# hvreg_feedback_2PS_FS_F.net
KiCad netlist of a schematic drawn in EAGLE
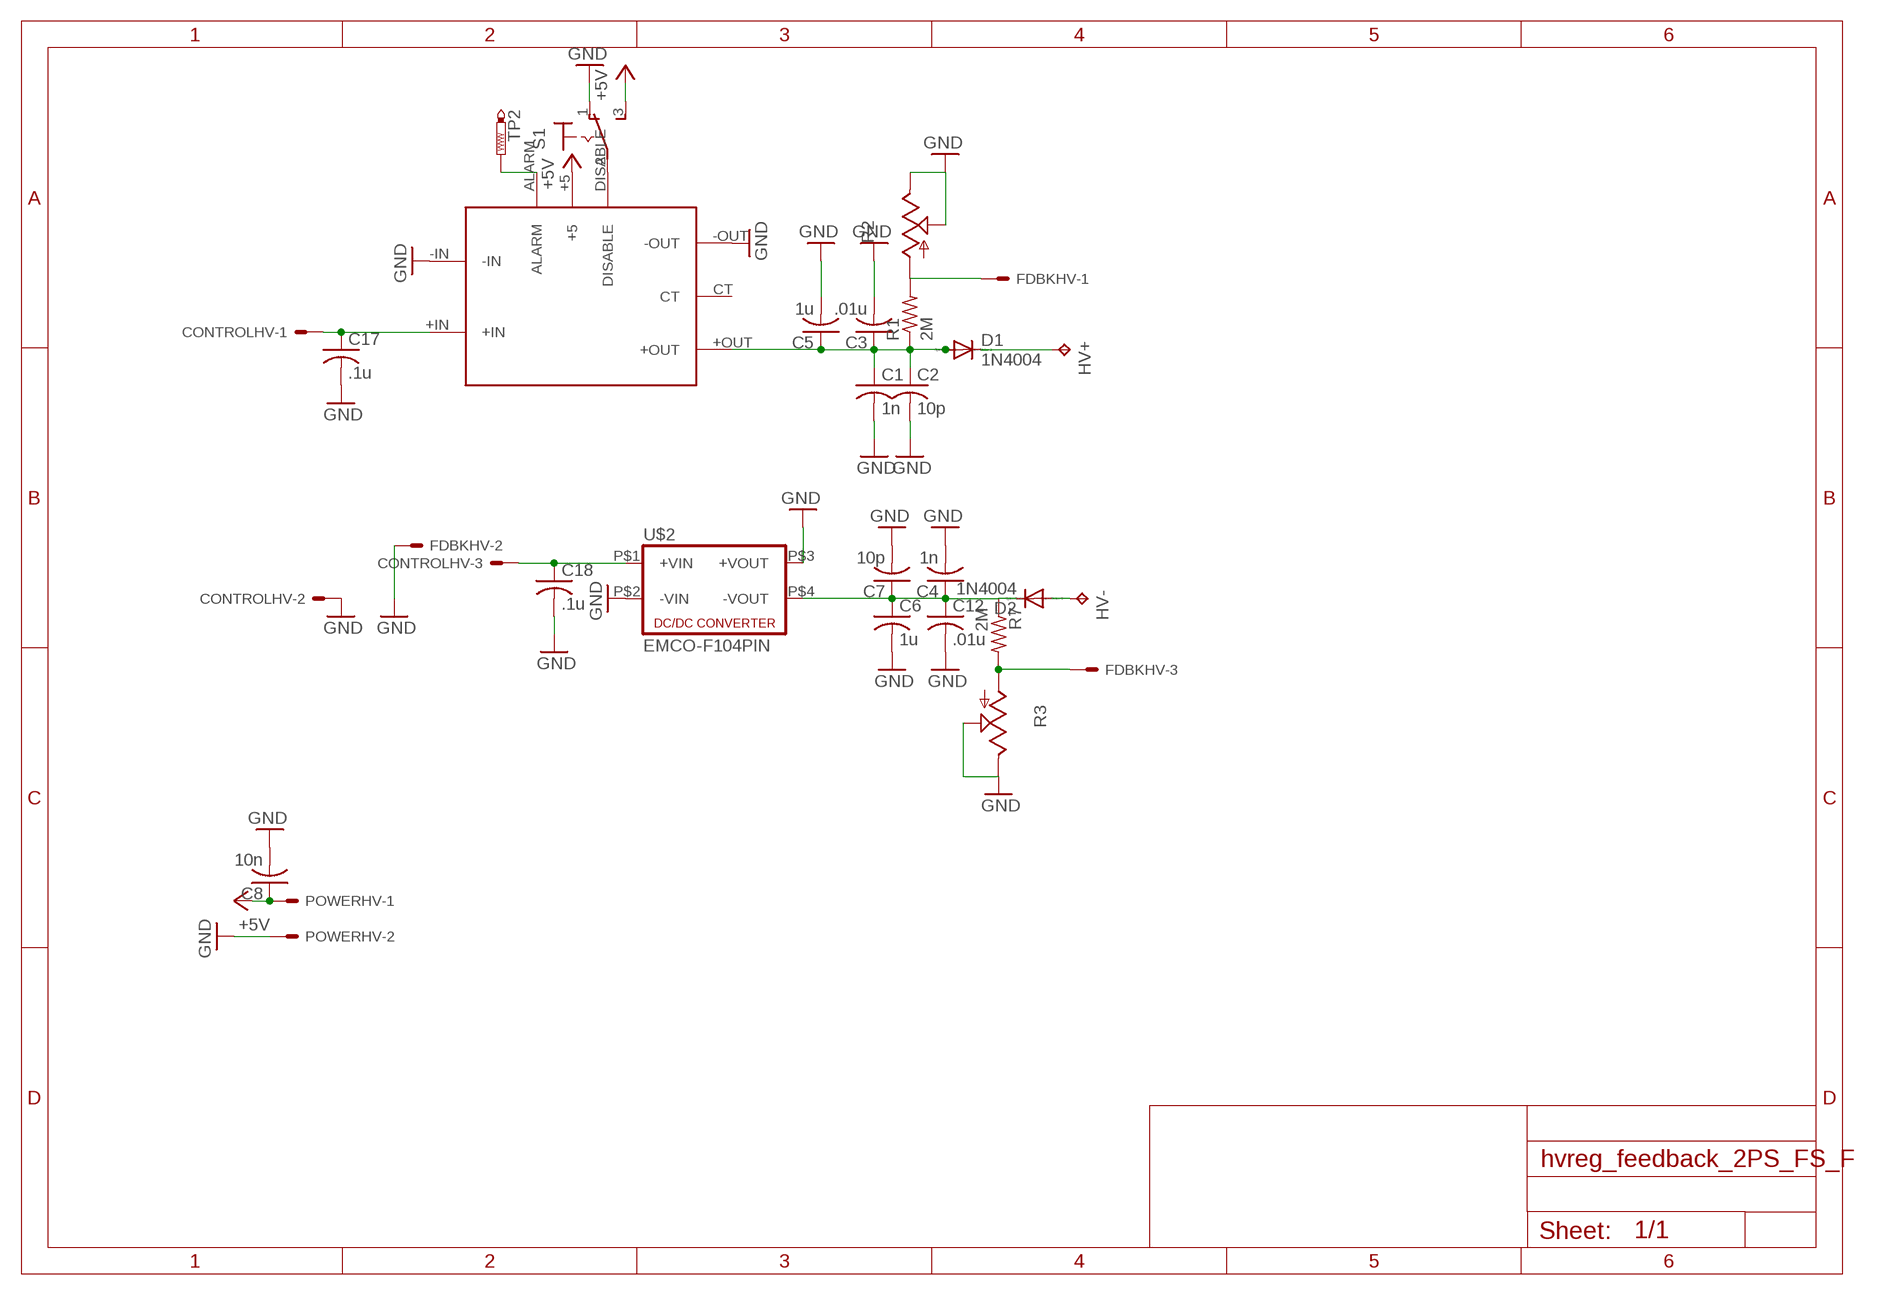
[diagram p0: schematic, sheet 1]

(export (version "E")
  (design (tool "Eeschema 10.0.6"))
  (components
    (comp (ref "C1")
      (value "1n")
      (footprint "eagle-import:C102-043X133")
      (libsource (lib "eagle-import") (part "C-US102-043X133"))
    )
    (comp (ref "C2")
      (value "10p")
      (footprint "eagle-import:C102-043X133")
      (libsource (lib "eagle-import") (part "C-US102-043X133"))
    )
    (comp (ref "C3")
      (value ".01u")
      (footprint "eagle-import:C102-043X133")
      (libsource (lib "eagle-import") (part "C-US102-043X133"))
    )
    (comp (ref "C4")
      (value "1n")
      (footprint "eagle-import:C102-043X133")
      (libsource (lib "eagle-import") (part "C-US102-043X133"))
    )
    (comp (ref "C5")
      (value "1u")
      (footprint "eagle-import:C275-205X316")
      (libsource (lib "eagle-import") (part "C-US275-205X316"))
    )
    (comp (ref "C6")
      (value "1u")
      (footprint "eagle-import:C275-205X316")
      (libsource (lib "eagle-import") (part "C-US275-205X316"))
    )
    (comp (ref "C7")
      (value "10p")
      (footprint "eagle-import:C102-043X133")
      (libsource (lib "eagle-import") (part "C-US102-043X133"))
    )
    (comp (ref "C8")
      (value "10n")
      (footprint "eagle-import:C050-024X044")
      (libsource (lib "eagle-import") (part "C-US050-024X044"))
    )
    (comp (ref "C12")
      (value ".01u")
      (footprint "eagle-import:C102-043X133")
      (libsource (lib "eagle-import") (part "C-US102-043X133"))
    )
    (comp (ref "C17")
      (value ".1u")
      (footprint "eagle-import:C225-113X268")
      (libsource (lib "eagle-import") (part "C-US225-113X268"))
    )
    (comp (ref "C18")
      (value ".1u")
      (footprint "eagle-import:C225-113X268")
      (libsource (lib "eagle-import") (part "C-US225-113X268"))
    )
    (comp (ref "CONTROLHV")
      (value "KK-156-3")
      (footprint "eagle-import:KK-156-3")
      (libsource (lib "eagle-import") (part "KK-156-3"))
    )
    (comp (ref "D1")
      (value "1N4004")
      (footprint "eagle-import:DO41-10")
      (libsource (lib "eagle-import") (part "1N4004"))
    )
    (comp (ref "D2")
      (value "1N4004")
      (footprint "eagle-import:DO41-10")
      (libsource (lib "eagle-import") (part "1N4004"))
    )
    (comp (ref "FDBKHV")
      (value "KK-156-3")
      (footprint "eagle-import:KK-156-3")
      (libsource (lib "eagle-import") (part "KK-156-3"))
    )
    (comp (ref "HV+")
      (value "TPPAD1-20Y")
      (footprint "eagle-import:P1-20Y")
      (libsource (lib "eagle-import") (part "TPPAD1-20Y"))
    )
    (comp (ref "HV-")
      (value "TPPAD1-20Y")
      (footprint "eagle-import:P1-20Y")
      (libsource (lib "eagle-import") (part "TPPAD1-20Y"))
    )
    (comp (ref "POWERHV")
      (value "KK-156-2")
      (footprint "eagle-import:KK-156-2")
      (libsource (lib "eagle-import") (part "KK-156-2"))
    )
    (comp (ref "R1")
      (value "2M")
      (footprint "eagle-import:P0613_15")
      (libsource (lib "eagle-import") (part "R-US_0613/15"))
    )
    (comp (ref "R2")
      (value "TRIM_US-B90P")
      (footprint "eagle-import:SP19L")
      (libsource (lib "eagle-import") (part "TRIM_US-B90P"))
    )
    (comp (ref "R3")
      (value "TRIM_US-B90P")
      (footprint "eagle-import:SP19L")
      (libsource (lib "eagle-import") (part "TRIM_US-B90P"))
    )
    (comp (ref "R7")
      (value "2M")
      (footprint "eagle-import:P0613_15")
      (libsource (lib "eagle-import") (part "R-US_0613/15"))
    )
    (comp (ref "S1")
      (value "M9040P")
      (footprint "eagle-import:M9040P")
      (libsource (lib "eagle-import") (part "M9040P"))
    )
    (comp (ref "TP2")
      (value "PTR1PAD1-20Y")
      (footprint "eagle-import:P1-20Y")
      (libsource (lib "eagle-import") (part "PTR1PAD1-20Y"))
    )
    (comp (ref "U$1")
      (value "EMCO-FS10")
      (footprint "eagle-import:EMCO-FS")
      (libsource (lib "eagle-import") (part "EMCO-FS10"))
    )
    (comp (ref "U$2")
      (value "EMCO-F104PIN")
      (footprint "eagle-import:EMCO-F")
      (libsource (lib "eagle-import") (part "EMCO-F104PIN"))
    )
  )
  (nets
    (net (code "1") (name "+5V") (class "Default")
      (node (ref "C8") (pin "1") (pinfunction "1_1") (pintype "passive"))
      (node (ref "POWERHV") (pin "1") (pinfunction "S_1") (pintype "passive"))
      (node (ref "S1") (pin "3") (pinfunction "S_3") (pintype "passive"))
      (node (ref "U$1") (pin "+5") (pinfunction "+5_+5") (pintype "bidirectional"))
    )
    (net (code "2") (name "GND") (class "Default")
      (node (ref "C1") (pin "2") (pinfunction "2_2") (pintype "passive"))
      (node (ref "C12") (pin "2") (pinfunction "2_2") (pintype "passive"))
      (node (ref "C17") (pin "2") (pinfunction "2_2") (pintype "passive"))
      (node (ref "C18") (pin "2") (pinfunction "2_2") (pintype "passive"))
      (node (ref "C2") (pin "2") (pinfunction "2_2") (pintype "passive"))
      (node (ref "C3") (pin "2") (pinfunction "2_2") (pintype "passive"))
      (node (ref "C4") (pin "2") (pinfunction "2_2") (pintype "passive"))
      (node (ref "C5") (pin "2") (pinfunction "2_2") (pintype "passive"))
      (node (ref "C6") (pin "2") (pinfunction "2_2") (pintype "passive"))
      (node (ref "C7") (pin "2") (pinfunction "2_2") (pintype "passive"))
      (node (ref "C8") (pin "2") (pinfunction "2_2") (pintype "passive"))
      (node (ref "CONTROLHV") (pin "2") (pinfunction "S_2") (pintype "passive"))
      (node (ref "FDBKHV") (pin "2") (pinfunction "S_2") (pintype "passive"))
      (node (ref "POWERHV") (pin "2") (pinfunction "S_2") (pintype "passive"))
      (node (ref "R2") (pin "E") (pinfunction "E_E") (pintype "passive"))
      (node (ref "R2") (pin "S") (pinfunction "S_S") (pintype "passive"))
      (node (ref "R3") (pin "E") (pinfunction "E_E") (pintype "passive"))
      (node (ref "R3") (pin "S") (pinfunction "S_S") (pintype "passive"))
      (node (ref "S1") (pin "1") (pinfunction "O_1") (pintype "passive"))
      (node (ref "U$1") (pin "-IN") (pinfunction "-IN_-IN") (pintype "bidirectional"))
      (node (ref "U$1") (pin "-OUT") (pinfunction "-OUT_-OUT") (pintype "bidirectional"))
      (node (ref "U$2") (pin "P$2") (pinfunction "-VIN_P$2") (pintype "passive"))
      (node (ref "U$2") (pin "P$3") (pinfunction "+VOUT_P$3") (pintype "passive"))
    )
    (net (code "3") (name "Net-(C1-Pad1)") (class "Default")
      (node (ref "C1") (pin "1") (pinfunction "1_1") (pintype "passive"))
      (node (ref "C2") (pin "1") (pinfunction "1_1") (pintype "passive"))
      (node (ref "C3") (pin "1") (pinfunction "1_1") (pintype "passive"))
      (node (ref "C5") (pin "1") (pinfunction "1_1") (pintype "passive"))
      (node (ref "D1") (pin "A") (pinfunction "A_A") (pintype "passive"))
      (node (ref "R1") (pin "1") (pinfunction "1_1") (pintype "passive"))
      (node (ref "U$1") (pin "+OUT") (pinfunction "+OUT_+OUT") (pintype "bidirectional"))
    )
    (net (code "4") (name "Net-(CONTROLHVA-S)") (class "Default")
      (node (ref "C17") (pin "1") (pinfunction "1_1") (pintype "passive"))
      (node (ref "CONTROLHV") (pin "1") (pinfunction "S_1") (pintype "passive"))
      (node (ref "U$1") (pin "+IN") (pinfunction "+IN_+IN") (pintype "bidirectional"))
    )
    (net (code "5") (name "Net-(CONTROLHVC-S)") (class "Default")
      (node (ref "C18") (pin "1") (pinfunction "1_1") (pintype "passive"))
      (node (ref "CONTROLHV") (pin "3") (pinfunction "S_3") (pintype "passive"))
      (node (ref "U$2") (pin "P$1") (pinfunction "+VIN_P$1") (pintype "passive"))
    )
    (net (code "6") (name "Net-(D1-PadC)") (class "Default")
      (node (ref "D1") (pin "C") (pinfunction "C_C") (pintype "passive"))
      (node (ref "HV+") (pin "TP") (pinfunction "TP_TP") (pintype "input"))
    )
    (net (code "7") (name "Net-(D2-PadA)") (class "Default")
      (node (ref "D2") (pin "A") (pinfunction "A_A") (pintype "passive"))
      (node (ref "HV-") (pin "TP") (pinfunction "TP_TP") (pintype "input"))
    )
    (net (code "8") (name "Net-(FDBKHVA-S)") (class "Default")
      (node (ref "FDBKHV") (pin "1") (pinfunction "S_1") (pintype "passive"))
      (node (ref "R1") (pin "2") (pinfunction "2_2") (pintype "passive"))
      (node (ref "R2") (pin "A") (pinfunction "A_A") (pintype "passive"))
    )
    (net (code "9") (name "Net-(FDBKHVC-S)") (class "Default")
      (node (ref "FDBKHV") (pin "3") (pinfunction "S_3") (pintype "passive"))
      (node (ref "R3") (pin "A") (pinfunction "A_A") (pintype "passive"))
      (node (ref "R7") (pin "2") (pinfunction "2_2") (pintype "passive"))
    )
    (net (code "10") (name "Net-(S1-P)") (class "Default")
      (node (ref "S1") (pin "2") (pinfunction "P_2") (pintype "passive"))
      (node (ref "U$1") (pin "DISABLE") (pinfunction "DISABLE_DISABLE") (pintype "bidirectional"))
    )
    (net (code "11") (name "Net-(TP2-PadTP)") (class "Default")
      (node (ref "TP2") (pin "TP") (pinfunction "TP_TP") (pintype "input"))
      (node (ref "U$1") (pin "ALARM") (pinfunction "ALARM_ALARM") (pintype "bidirectional"))
    )
    (net (code "12") (name "Net-(U$2--VOUT)") (class "Default")
      (node (ref "C12") (pin "1") (pinfunction "1_1") (pintype "passive"))
      (node (ref "C4") (pin "1") (pinfunction "1_1") (pintype "passive"))
      (node (ref "C6") (pin "1") (pinfunction "1_1") (pintype "passive"))
      (node (ref "C7") (pin "1") (pinfunction "1_1") (pintype "passive"))
      (node (ref "D2") (pin "C") (pinfunction "C_C") (pintype "passive"))
      (node (ref "R7") (pin "1") (pinfunction "1_1") (pintype "passive"))
      (node (ref "U$2") (pin "P$4") (pinfunction "-VOUT_P$4") (pintype "passive"))
    )
    (net (code "13") (name "unconnected-(U$1-PadCT)") (class "Default")
      (node (ref "U$1") (pin "CT") (pinfunction "CT_CT") (pintype "bidirectional"))
    )
  )
)
